# downConverter.net
KiCad netlist of a schematic drawn in Altium Designer
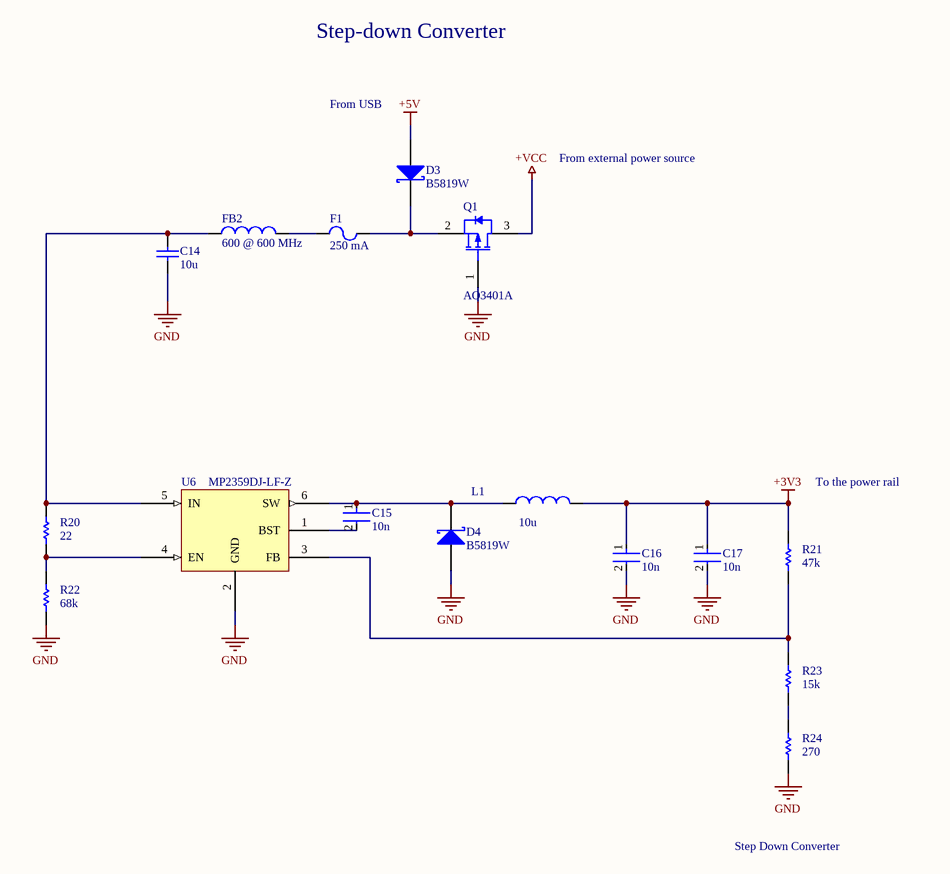
[diagram p0: downConverter.SchDoc]

(export (version "E")
  (design (tool "Eeschema 10.0.6"))
  (components
    (comp (ref "C14")
      (value "10u")
      (footprint "Capacitor 1206")
      (description "Chip Capacitor, 1206")
      (fields
        (field (name "MANUFACTURER") "Murata")
        (field (name "MANUFACTURER PART NUMBER") "GRM1885C1H220JA01D")
      )
      (libsource (lib "F4_Flight_Controller") (part "Capacitor 1206"))
    )
    (comp (ref "C15")
      (value "10n")
      (footprint "Capacitor 0402")
      (description "Chip Capacitor 0402")
      (fields (field (name "MANUFACTURER PART NUMBER") "CC0402KRX7R7BB103") (field (name "TOLERANCE") "0.1"))
      (libsource (lib "F4_Flight_Controller") (part "Capacitor 0402"))
    )
    (comp (ref "C16")
      (value "10n")
      (footprint "Capacitor 0402")
      (description "Chip Capacitor 0402")
      (fields (field (name "MANUFACTURER PART NUMBER") "CC0402KRX7R7BB103") (field (name "TOLERANCE") "0.1"))
      (libsource (lib "F4_Flight_Controller") (part "Capacitor 0402"))
    )
    (comp (ref "C17")
      (value "10n")
      (footprint "Capacitor 0402")
      (description "Chip Capacitor 0402")
      (fields (field (name "MANUFACTURER PART NUMBER") "CC0402KRX7R7BB103") (field (name "TOLERANCE") "0.1"))
      (libsource (lib "F4_Flight_Controller") (part "Capacitor 0402"))
    )
    (comp (ref "D3")
      (value "B5819W")
      (footprint "SOD3716X135N")
      (description "Schottky Barrier Rectifier, 20 V, 1 A, -65 to 150 degC, 2-Pin DO-214AC (SMA), RoHS, Tape and Reel")
      (fields
        (field (name "MANUFACTURER") "Vishay Intertechnology")
        (field (name "MANUFACTURER PART NUMBER") "SS12-E~{3}61T")
      )
      (libsource (lib "F4_Flight_Controller") (part "Schottky Barrier Rectifier"))
    )
    (comp (ref "D4")
      (value "B5819W")
      (footprint "SOD3716X135N")
      (description "Schottky Barrier Rectifier, 20 V, 1 A, -65 to 150 degC, 2-Pin DO-214AC (SMA), RoHS, Tape and Reel")
      (fields
        (field (name "MANUFACTURER") "Vishay Intertechnology")
        (field (name "MANUFACTURER PART NUMBER") "SS12-E~{3}61T")
      )
      (libsource (lib "F4_Flight_Controller") (part "Schottky Barrier Rectifier"))
    )
    (comp (ref "F1")
      (value "250 mA")
      (footprint "Fuse 1206")
      (description "NANO2(R) Slo-Blo(R) Fuse, 0.5 A, 125 V, -55 to 125 degC, 2-Pin SMD, RoHS, Tape and Reel")
      (fields
        (field (name "MANUFACTURER") "Littelfuse")
        (field (name "MANUFACTURER PART NUMBER") "0452.500MRL")
      )
      (libsource (lib "F4_Flight_Controller") (part "Fuse 1206"))
    )
    (comp (ref "FB2")
      (value "600 @ 600 MHz")
      (footprint "Inductor 0805")
      (description "Ferrite Bead Murata BLM21AG601SN1D")
      (fields
        (field (name "MANUFACTURER") "TDK")
        (field (name "MANUFACTURER PART NUMBER") "MLZ2012A1R0MT000")
      )
      (libsource (lib "F4_Flight_Controller") (part "Ferrite Bead"))
    )
    (comp (ref "L1")
      (value "10u")
      (footprint "LQH32DN100K23L")
      (description "LQH32CN100K33L 10uh")
      (fields
        (field (name "MANUFACTURER") "TDK")
        (field (name "MANUFACTURER PART NUMBER") "MLZ2012A1R0MT000")
      )
      (libsource (lib "F4_Flight_Controller") (part "Fixed Inductor"))
    )
    (comp (ref "Q1")
      (value "AO3401A")
      (footprint "SOT95P245X110-3N")
      (description "P-Channel MOSFET, 30 V, 4 A, -55 to 150 degC, 3-Pin SOT-23-3L, RoHS, Tape and Reel")
      (fields (field (name "MANUFACTURER") "Alpha & Omega Semiconductor"))
      (libsource (lib "F4_Flight_Controller") (part "P-Channel MOSFET"))
    )
    (comp (ref "R20")
      (value "22")
      (footprint "RESISTOR 0603")
      (description "Chip Resistor 0603")
      (fields (field (name "MANUFACTURER") "Vishay") (field (name "PART NUMBER") "CRCW0402120RFKED"))
      (libsource (lib "F4_Flight_Controller") (part "Resistor 0603"))
    )
    (comp (ref "R21")
      (value "47k")
      (footprint "RESISTOR 0603")
      (description "Chip Resistor 0603")
      (fields (field (name "MANUFACTURER") "Vishay") (field (name "PART NUMBER") "CRCW0402120RFKED"))
      (libsource (lib "F4_Flight_Controller") (part "Resistor 0603"))
    )
    (comp (ref "R22")
      (value "68k")
      (footprint "RESISTOR 0603")
      (description "Chip Resistor 0603")
      (fields (field (name "MANUFACTURER") "Vishay") (field (name "PART NUMBER") "CRCW0402120RFKED"))
      (libsource (lib "F4_Flight_Controller") (part "Resistor 0603"))
    )
    (comp (ref "R23")
      (value "15k")
      (footprint "RESISTOR 0603")
      (description "Chip Resistor 0603")
      (fields (field (name "MANUFACTURER") "Vishay") (field (name "PART NUMBER") "CRCW0402120RFKED"))
      (libsource (lib "F4_Flight_Controller") (part "Resistor 0603"))
    )
    (comp (ref "R24")
      (value "270")
      (footprint "RESISTOR 0603")
      (description "Chip Resistor 0603")
      (fields (field (name "MANUFACTURER") "Vishay") (field (name "PART NUMBER") "CRCW0402120RFKED"))
      (libsource (lib "F4_Flight_Controller") (part "Resistor 0603"))
    )
    (comp (ref "U6")
      (value "MP2359DJ-LF-Z")
      (footprint "SOT95P280X100-6N")
      (description "Regulator")
      (libsource (lib "F4_Flight_Controller") (part "MP2359DJ-LF-Z"))
    )
  )
  (nets
    (net (code "1") (name "+3V3") (class "Default")
      (node (ref "C16") (pin "1") (pinfunction "1_1") (pintype "passive"))
      (node (ref "C17") (pin "1") (pinfunction "1_1") (pintype "passive"))
      (node (ref "L1") (pin "2") (pinfunction "2_2") (pintype "passive"))
      (node (ref "R21") (pin "2") (pinfunction "2_2") (pintype "passive"))
    )
    (net (code "2") (name "+5V") (class "Default")
      (node (ref "D3") (pin "1") (pinfunction "A_1") (pintype "passive"))
    )
    (net (code "3") (name "+VCC") (class "Default")
      (node (ref "Q1") (pin "3") (pinfunction "DRAIN_3") (pintype "passive"))
    )
    (net (code "4") (name "GND") (class "Default")
      (node (ref "C14") (pin "1") (pinfunction "1_1") (pintype "passive"))
      (node (ref "C16") (pin "2") (pinfunction "2_2") (pintype "passive"))
      (node (ref "C17") (pin "2") (pinfunction "2_2") (pintype "passive"))
      (node (ref "D4") (pin "1") (pinfunction "A_1") (pintype "passive"))
      (node (ref "Q1") (pin "1") (pinfunction "GATE_1") (pintype "passive"))
      (node (ref "R22") (pin "1") (pinfunction "1_1") (pintype "passive"))
      (node (ref "R24") (pin "1") (pinfunction "1_1") (pintype "passive"))
      (node (ref "U6") (pin "2") (pinfunction "GND_2") (pintype "passive"))
    )
    (net (code "5") (name "Net-(D3-K)") (class "Default")
      (node (ref "D3") (pin "2") (pinfunction "K_2") (pintype "passive"))
      (node (ref "F1") (pin "2") (pinfunction "2_2") (pintype "passive"))
      (node (ref "Q1") (pin "2") (pinfunction "SOURCE_2") (pintype "passive"))
    )
    (net (code "6") (name "Net-(D4-K)") (class "Default")
      (node (ref "C15") (pin "1") (pinfunction "1_1") (pintype "passive"))
      (node (ref "D4") (pin "2") (pinfunction "K_2") (pintype "passive"))
      (node (ref "L1") (pin "1") (pinfunction "1_1") (pintype "passive"))
      (node (ref "U6") (pin "6") (pinfunction "SW_6") (pintype "output"))
    )
    (net (code "7") (name "Net-(F1-Pad1)") (class "Default")
      (node (ref "F1") (pin "1") (pinfunction "1_1") (pintype "passive"))
      (node (ref "FB2") (pin "2") (pinfunction "2_2") (pintype "passive"))
    )
    (net (code "8") (name "Net-(R23-Pad1)") (class "Default")
      (node (ref "R23") (pin "1") (pinfunction "1_1") (pintype "passive"))
      (node (ref "R24") (pin "2") (pinfunction "2_2") (pintype "passive"))
    )
    (net (code "9") (name "Net-(U6-BST)") (class "Default")
      (node (ref "C15") (pin "2") (pinfunction "2_2") (pintype "passive"))
      (node (ref "U6") (pin "1") (pinfunction "BST_1") (pintype "passive"))
    )
    (net (code "10") (name "Net-(U6-EN)") (class "Default")
      (node (ref "R20") (pin "1") (pinfunction "1_1") (pintype "passive"))
      (node (ref "R22") (pin "2") (pinfunction "2_2") (pintype "passive"))
      (node (ref "U6") (pin "4") (pinfunction "EN_4") (pintype "input"))
    )
    (net (code "11") (name "Net-(U6-FB)") (class "Default")
      (node (ref "R21") (pin "1") (pinfunction "1_1") (pintype "passive"))
      (node (ref "R23") (pin "2") (pinfunction "2_2") (pintype "passive"))
      (node (ref "U6") (pin "3") (pinfunction "FB_3") (pintype "passive"))
    )
    (net (code "12") (name "Net-(U6-IN)") (class "Default")
      (node (ref "C14") (pin "2") (pinfunction "2_2") (pintype "passive"))
      (node (ref "FB2") (pin "1") (pinfunction "1_1") (pintype "passive"))
      (node (ref "R20") (pin "2") (pinfunction "2_2") (pintype "passive"))
      (node (ref "U6") (pin "5") (pinfunction "IN_5") (pintype "input"))
    )
  )
)
